# 1-POWER.net
KiCad netlist of a schematic drawn in Altium Designer
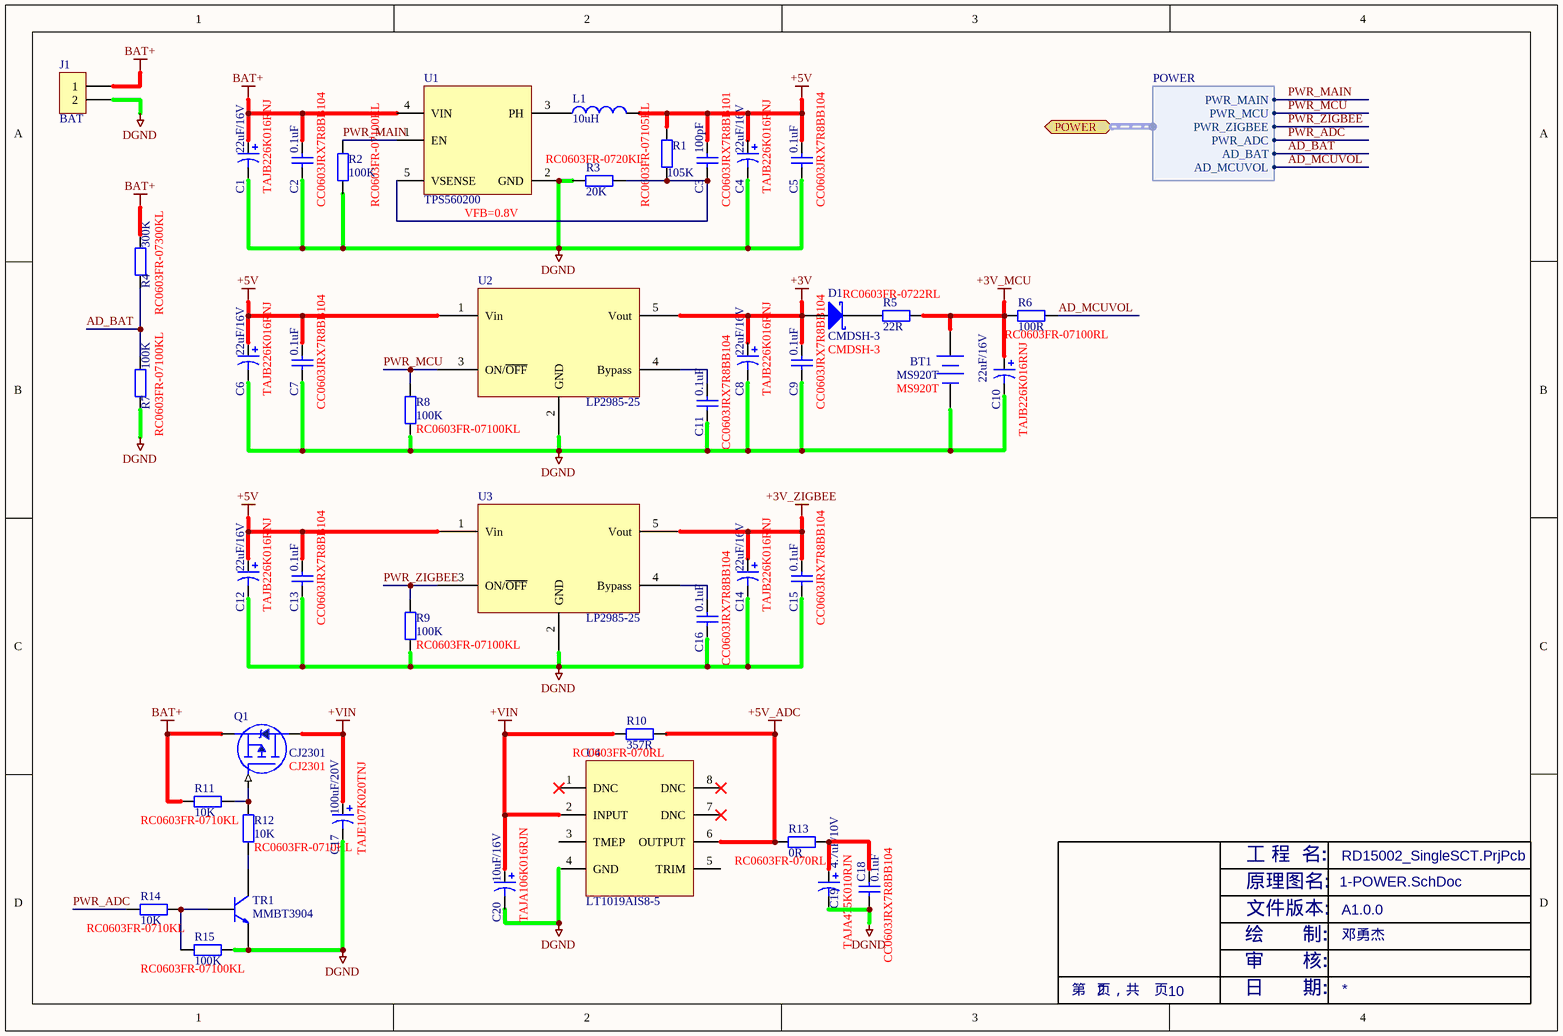
[diagram p0: 1-POWER.SchDoc]

(export (version "E")
  (design (tool "Eeschema 10.0.6"))
  (components
    (comp (ref "BT1")
      (value "MS920T")
      (footprint "MS920T")
      (description "Multicell Battery")
      (fields (field (name "TYPE NO.") "MS920T"))
      (libsource (lib "Miscellaneous Devices") (part "Battery"))
    )
    (comp (ref "C1")
      (value "22uF/16V")
      (footprint "CB3528")
      (description "Polarized Capacitor (Radial)")
      (fields (field (name "PART NO.") "TAJB226K016RNJ"))
      (libsource (lib "Miscellaneous Devices") (part "Cap Pol1"))
    )
    (comp (ref "C2")
      (value "0.1uF")
      (footprint "CC0603")
      (description "Capacitor")
      (fields (field (name "TYPE NO.") "CC0603JRX7R8BB104"))
      (libsource (lib "Miscellaneous Devices") (part "Cap"))
    )
    (comp (ref "C3")
      (value "100pF")
      (footprint "CC0603")
      (description "Capacitor")
      (fields (field (name "TYPE NO.") "CC0603JRX7R8BB101"))
      (libsource (lib "Miscellaneous Devices") (part "Cap"))
    )
    (comp (ref "C4")
      (value "22uF/16V")
      (footprint "CB3528")
      (description "Polarized Capacitor (Radial)")
      (fields (field (name "PART NO.") "TAJB226K016RNJ"))
      (libsource (lib "Miscellaneous Devices") (part "Cap Pol1"))
    )
    (comp (ref "C5")
      (value "0.1uF")
      (footprint "CC0603")
      (description "Capacitor")
      (fields (field (name "TYPE NO.") "CC0603JRX7R8BB104"))
      (libsource (lib "Miscellaneous Devices") (part "Cap"))
    )
    (comp (ref "C6")
      (value "22uF/16V")
      (footprint "CB3528")
      (description "Polarized Capacitor (Radial)")
      (fields (field (name "PART NO.") "TAJB226K016RNJ"))
      (libsource (lib "Miscellaneous Devices") (part "Cap Pol1"))
    )
    (comp (ref "C7")
      (value "0.1uF")
      (footprint "CC0603")
      (description "Capacitor")
      (fields (field (name "TYPE NO.") "CC0603JRX7R8BB104"))
      (libsource (lib "Miscellaneous Devices") (part "Cap"))
    )
    (comp (ref "C8")
      (value "22uF/16V")
      (footprint "CB3528")
      (description "Polarized Capacitor (Radial)")
      (fields (field (name "PART NO.") "TAJB226K016RNJ"))
      (libsource (lib "Miscellaneous Devices") (part "Cap Pol1"))
    )
    (comp (ref "C9")
      (value "0.1uF")
      (footprint "CC0603")
      (description "Capacitor")
      (fields (field (name "TYPE NO.") "CC0603JRX7R8BB104"))
      (libsource (lib "Miscellaneous Devices") (part "Cap"))
    )
    (comp (ref "C10")
      (value "22uF/16V")
      (footprint "CB3528")
      (description "Polarized Capacitor (Radial)")
      (fields (field (name "PART NO.") "TAJB226K016RNJ"))
      (libsource (lib "Miscellaneous Devices") (part "Cap Pol1"))
    )
    (comp (ref "C11")
      (value "0.1uF")
      (footprint "CC0603")
      (description "Capacitor")
      (fields (field (name "TYPE NO.") "CC0603JRX7R8BB104"))
      (libsource (lib "Miscellaneous Devices") (part "Cap"))
    )
    (comp (ref "C12")
      (value "22uF/16V")
      (footprint "CB3528")
      (description "Polarized Capacitor (Radial)")
      (fields (field (name "PART NO.") "TAJB226K016RNJ"))
      (libsource (lib "Miscellaneous Devices") (part "Cap Pol1"))
    )
    (comp (ref "C13")
      (value "0.1uF")
      (footprint "CC0603")
      (description "Capacitor")
      (fields (field (name "TYPE NO.") "CC0603JRX7R8BB104"))
      (libsource (lib "Miscellaneous Devices") (part "Cap"))
    )
    (comp (ref "C14")
      (value "22uF/16V")
      (footprint "CB3528")
      (description "Polarized Capacitor (Radial)")
      (fields (field (name "PART NO.") "TAJB226K016RNJ"))
      (libsource (lib "Miscellaneous Devices") (part "Cap Pol1"))
    )
    (comp (ref "C15")
      (value "0.1uF")
      (footprint "CC0603")
      (description "Capacitor")
      (fields (field (name "TYPE NO.") "CC0603JRX7R8BB104"))
      (libsource (lib "Miscellaneous Devices") (part "Cap"))
    )
    (comp (ref "C16")
      (value "0.1uF")
      (footprint "CC0603")
      (description "Capacitor")
      (fields (field (name "TYPE NO.") "CC0603JRX7R8BB104"))
      (libsource (lib "Miscellaneous Devices") (part "Cap"))
    )
    (comp (ref "C17")
      (value "100uF/20V")
      (footprint "CD7343")
      (description "Polarized Capacitor (Surface Mount)")
      (fields (field (name "TYPE NO.") "TAJE107K020TNJ"))
      (libsource (lib "Miscellaneous Devices") (part "Cap Pol3"))
    )
    (comp (ref "C18")
      (value "0.1uF")
      (footprint "CC0603")
      (description "Capacitor")
      (fields (field (name "TYPE NO.") "CC0603JRX7R8BB104"))
      (libsource (lib "Miscellaneous Devices") (part "Cap"))
    )
    (comp (ref "C19")
      (value "4.7uF/10V")
      (footprint "CA3216")
      (description "Polarized Capacitor (Radial)")
      (fields (field (name "TYPE NO.") "TAJA475K010RJN"))
      (libsource (lib "Miscellaneous Devices") (part "Cap Pol1"))
    )
    (comp (ref "C20")
      (value "10uF/16V")
      (footprint "CA3216")
      (description "Polarized Capacitor (Radial)")
      (fields (field (name "TYPE NO.") "TAJA106K016RJN"))
      (libsource (lib "Miscellaneous Devices") (part "Cap Pol1"))
    )
    (comp (ref "D1")
      (value "CMDSH-3")
      (footprint "SOD323")
      (description "Schottky Diode")
      (fields (field (name "TYPE NO.") "CMDSH-3"))
      (libsource (lib "Miscellaneous Devices") (part "D Schottky"))
    )
    (comp (ref "J1")
      (value "BAT")
      (footprint "CON2-2.54MM")
      (description "jointbar")
      (libsource (lib "AD9_WOY") (part "SIP2"))
    )
    (comp (ref "L1")
      (value "10uH")
      (footprint "SLF6025")
      (description "Inductor")
      (fields (field (name "PUBLISHER") "Altium Limited"))
      (libsource (lib "Miscellaneous Devices") (part "Inductor"))
    )
    (comp (ref "Q1")
      (value "CJ2301")
      (footprint "SOT-23W")
      (fields (field (name "TYPE NO.") "CJ2301"))
      (libsource (lib "woylib2015") (part "P-MOSFET1"))
    )
    (comp (ref "R1")
      (value "105K")
      (footprint "CC0603")
      (description "Resistor")
      (fields (field (name "TYPE NO.") "RC0603FR-07105KL"))
      (libsource (lib "") (part "Res2_1"))
    )
    (comp (ref "R2")
      (value "100K")
      (footprint "CC0603")
      (description "Resistor")
      (fields (field (name "TYPE NO.") "RC0603FR-07100KL"))
      (libsource (lib "") (part "Res2_1"))
    )
    (comp (ref "R3")
      (value "20K")
      (footprint "CC0603")
      (description "Resistor")
      (fields (field (name "TYPE NO.") "RC0603FR-0720KL"))
      (libsource (lib "Miscellaneous Devices") (part "Res2"))
    )
    (comp (ref "R4")
      (value "300K")
      (footprint "CC0603")
      (description "Resistor")
      (fields (field (name "TYPE NO.") "RC0603FR-07300KL"))
      (libsource (lib "") (part "Res2_1"))
    )
    (comp (ref "R5")
      (value "22R")
      (footprint "CC0603")
      (description "Resistor")
      (fields (field (name "TYPE NO.") "RC0603FR-0722RL"))
      (libsource (lib "Miscellaneous Devices") (part "Res2"))
    )
    (comp (ref "R6")
      (value "100R")
      (footprint "CC0603")
      (description "Resistor")
      (fields (field (name "TYPE NO.") "RC0603FR-07100RL"))
      (libsource (lib "Miscellaneous Devices") (part "Res2"))
    )
    (comp (ref "R7")
      (value "100K")
      (footprint "CC0603")
      (description "Resistor")
      (fields (field (name "TYPE NO.") "RC0603FR-07100KL"))
      (libsource (lib "") (part "Res2_1"))
    )
    (comp (ref "R8")
      (value "100K")
      (footprint "CC0603")
      (description "Resistor")
      (fields (field (name "TYPE NO.") "RC0603FR-07100KL"))
      (libsource (lib "") (part "Res2_1"))
    )
    (comp (ref "R9")
      (value "100K")
      (footprint "CC0603")
      (description "Resistor")
      (fields (field (name "TYPE NO.") "RC0603FR-07100KL"))
      (libsource (lib "") (part "Res2_1"))
    )
    (comp (ref "R10")
      (value "357R")
      (footprint "CC0603")
      (description "Resistor")
      (fields (field (name "TYPE NO.") "RC0603FR-070RL"))
      (libsource (lib "Miscellaneous Devices") (part "Res2"))
    )
    (comp (ref "R11")
      (value "10K")
      (footprint "CC0603")
      (description "Resistor")
      (fields (field (name "TYPE NO.") "RC0603FR-0710KL"))
      (libsource (lib "Miscellaneous Devices") (part "Res2"))
    )
    (comp (ref "R12")
      (value "10K")
      (footprint "CC0603")
      (description "Resistor")
      (fields (field (name "TYPE NO.") "RC0603FR-0710KL"))
      (libsource (lib "") (part "Res2_1"))
    )
    (comp (ref "R13")
      (value "0R")
      (footprint "CC0603")
      (description "Resistor")
      (fields (field (name "TYPE NO.") "RC0603FR-070RL"))
      (libsource (lib "Miscellaneous Devices") (part "Res2"))
    )
    (comp (ref "R14")
      (value "10K")
      (footprint "CC0603")
      (description "Resistor")
      (fields (field (name "TYPE NO.") "RC0603FR-0710KL"))
      (libsource (lib "Miscellaneous Devices") (part "Res2"))
    )
    (comp (ref "R15")
      (value "100K")
      (footprint "CC0603")
      (description "Resistor")
      (fields (field (name "TYPE NO.") "RC0603FR-07100KL"))
      (libsource (lib "Miscellaneous Devices") (part "Res2"))
    )
    (comp (ref "TR1") (value "MMBT3904") (footprint "SOT-23W") (libsource (lib "Discrete") (part "NPN")))
    (comp (ref "U1") (value "TPS560200") (footprint "SOT-23-5") (libsource (lib "IC") (part "TPS560200")))
    (comp (ref "U2") (value "LP2985-25") (footprint "SOT-23-5") (libsource (lib "IC") (part "LP2985")))
    (comp (ref "U3") (value "LP2985-25") (footprint "SOT-23-5") (libsource (lib "IC") (part "LP2985")))
    (comp (ref "U4") (value "LT1019AIS8-5") (footprint "SO-8") (libsource (lib "IC") (part "LT1019AIS8-5")))
  )
  (nets
    (net (code "2") (name "+3V") (class "Default")
      (node (ref "C8") (pin "1") (pinfunction "1_1") (pintype "passive"))
      (node (ref "C9") (pin "2") (pinfunction "2_2") (pintype "passive"))
      (node (ref "D1") (pin "1") (pinfunction "A_1") (pintype "passive"))
      (node (ref "U2") (pin "5") (pinfunction "Vout_5") (pintype "passive"))
    )
    (net (code "3") (name "+3V_MCU") (class "Default")
      (node (ref "BT1") (pin "1") (pinfunction "+_1") (pintype "passive"))
      (node (ref "C10") (pin "1") (pinfunction "1_1") (pintype "passive"))
      (node (ref "R5") (pin "1") (pinfunction "1_1") (pintype "passive"))
      (node (ref "R6") (pin "2") (pinfunction "2_2") (pintype "passive"))
    )
    (net (code "4") (name "+3V_ZIGBEE") (class "Default")
      (node (ref "C14") (pin "1") (pinfunction "1_1") (pintype "passive"))
      (node (ref "C15") (pin "2") (pinfunction "2_2") (pintype "passive"))
      (node (ref "U3") (pin "5") (pinfunction "Vout_5") (pintype "passive"))
    )
    (net (code "5") (name "+5V") (class "Default")
      (node (ref "C12") (pin "1") (pinfunction "1_1") (pintype "passive"))
      (node (ref "C13") (pin "2") (pinfunction "2_2") (pintype "passive"))
      (node (ref "C3") (pin "2") (pinfunction "2_2") (pintype "passive"))
      (node (ref "C4") (pin "1") (pinfunction "1_1") (pintype "passive"))
      (node (ref "C5") (pin "2") (pinfunction "2_2") (pintype "passive"))
      (node (ref "C6") (pin "1") (pinfunction "1_1") (pintype "passive"))
      (node (ref "C7") (pin "2") (pinfunction "2_2") (pintype "passive"))
      (node (ref "L1") (pin "2") (pinfunction "2_2") (pintype "passive"))
      (node (ref "R1") (pin "1") (pinfunction "1_1") (pintype "passive"))
      (node (ref "U2") (pin "1") (pinfunction "Vin_1") (pintype "passive"))
      (node (ref "U3") (pin "1") (pinfunction "Vin_1") (pintype "passive"))
    )
    (net (code "6") (name "+5V_ADC") (class "Default")
      (node (ref "R10") (pin "1") (pinfunction "1_1") (pintype "passive"))
      (node (ref "R13") (pin "2") (pinfunction "2_2") (pintype "passive"))
      (node (ref "U4") (pin "6") (pinfunction "OUTPUT_6") (pintype "passive"))
    )
    (net (code "7") (name "+VIN") (class "Default")
      (node (ref "C17") (pin "1") (pinfunction "1_1") (pintype "passive"))
      (node (ref "C20") (pin "1") (pinfunction "1_1") (pintype "passive"))
      (node (ref "Q1") (pin "3") (pinfunction "DRAIN_3") (pintype "passive"))
      (node (ref "R10") (pin "2") (pinfunction "2_2") (pintype "passive"))
      (node (ref "U4") (pin "2") (pinfunction "INPUT_2") (pintype "passive"))
    )
    (net (code "8") (name "/AD_BAT") (class "Default")
      (node (ref "R4") (pin "2") (pinfunction "2_2") (pintype "passive"))
      (node (ref "R7") (pin "1") (pinfunction "1_1") (pintype "passive"))
    )
    (net (code "9") (name "/AD_MCUVOL") (class "Default")
      (node (ref "R6") (pin "1") (pinfunction "1_1") (pintype "passive"))
    )
    (net (code "10") (name "/PWR_ADC") (class "Default")
      (node (ref "R14") (pin "2") (pinfunction "2_2") (pintype "passive"))
    )
    (net (code "11") (name "/PWR_MAIN") (class "Default")
      (node (ref "R2") (pin "1") (pinfunction "1_1") (pintype "passive"))
      (node (ref "U1") (pin "1") (pinfunction "EN_1") (pintype "passive"))
    )
    (net (code "12") (name "/PWR_MCU") (class "Default")
      (node (ref "R8") (pin "1") (pinfunction "1_1") (pintype "passive"))
      (node (ref "U2") (pin "3") (pinfunction "ON/~{OFF}_3") (pintype "passive"))
    )
    (net (code "13") (name "/PWR_ZIGBEE") (class "Default")
      (node (ref "R9") (pin "1") (pinfunction "1_1") (pintype "passive"))
      (node (ref "U3") (pin "3") (pinfunction "ON/~{OFF}_3") (pintype "passive"))
    )
    (net (code "15") (name "BAT+") (class "Default")
      (node (ref "C1") (pin "1") (pinfunction "1_1") (pintype "passive"))
      (node (ref "C2") (pin "2") (pinfunction "2_2") (pintype "passive"))
      (node (ref "J1") (pin "1") (pinfunction "1_1") (pintype "passive"))
      (node (ref "Q1") (pin "2") (pinfunction "SOURCE_2") (pintype "passive"))
      (node (ref "R11") (pin "2") (pinfunction "2_2") (pintype "passive"))
      (node (ref "R4") (pin "1") (pinfunction "1_1") (pintype "passive"))
      (node (ref "U1") (pin "4") (pinfunction "VIN_4") (pintype "passive"))
    )
    (net (code "16") (name "DGND") (class "Default")
      (node (ref "BT1") (pin "2") (pinfunction "-_2") (pintype "passive"))
      (node (ref "C1") (pin "2") (pinfunction "2_2") (pintype "passive"))
      (node (ref "C10") (pin "2") (pinfunction "2_2") (pintype "passive"))
      (node (ref "C11") (pin "1") (pinfunction "1_1") (pintype "passive"))
      (node (ref "C12") (pin "2") (pinfunction "2_2") (pintype "passive"))
      (node (ref "C13") (pin "1") (pinfunction "1_1") (pintype "passive"))
      (node (ref "C14") (pin "2") (pinfunction "2_2") (pintype "passive"))
      (node (ref "C15") (pin "1") (pinfunction "1_1") (pintype "passive"))
      (node (ref "C16") (pin "1") (pinfunction "1_1") (pintype "passive"))
      (node (ref "C17") (pin "2") (pinfunction "2_2") (pintype "passive"))
      (node (ref "C18") (pin "1") (pinfunction "1_1") (pintype "passive"))
      (node (ref "C19") (pin "2") (pinfunction "2_2") (pintype "passive"))
      (node (ref "C2") (pin "1") (pinfunction "1_1") (pintype "passive"))
      (node (ref "C20") (pin "2") (pinfunction "2_2") (pintype "passive"))
      (node (ref "C4") (pin "2") (pinfunction "2_2") (pintype "passive"))
      (node (ref "C5") (pin "1") (pinfunction "1_1") (pintype "passive"))
      (node (ref "C6") (pin "2") (pinfunction "2_2") (pintype "passive"))
      (node (ref "C7") (pin "1") (pinfunction "1_1") (pintype "passive"))
      (node (ref "C8") (pin "2") (pinfunction "2_2") (pintype "passive"))
      (node (ref "C9") (pin "1") (pinfunction "1_1") (pintype "passive"))
      (node (ref "J1") (pin "2") (pinfunction "2_2") (pintype "passive"))
      (node (ref "R15") (pin "1") (pinfunction "1_1") (pintype "passive"))
      (node (ref "R2") (pin "2") (pinfunction "2_2") (pintype "passive"))
      (node (ref "R3") (pin "2") (pinfunction "2_2") (pintype "passive"))
      (node (ref "R7") (pin "2") (pinfunction "2_2") (pintype "passive"))
      (node (ref "R8") (pin "2") (pinfunction "2_2") (pintype "passive"))
      (node (ref "R9") (pin "2") (pinfunction "2_2") (pintype "passive"))
      (node (ref "TR1") (pin "2") (pinfunction "2_2") (pintype "passive"))
      (node (ref "U1") (pin "2") (pinfunction "GND_2") (pintype "passive"))
      (node (ref "U2") (pin "2") (pinfunction "GND_2") (pintype "passive"))
      (node (ref "U3") (pin "2") (pinfunction "GND_2") (pintype "passive"))
      (node (ref "U4") (pin "4") (pinfunction "GND_4") (pintype "passive"))
    )
    (net (code "17") (name "Net-(C18-Pad2)") (class "Default")
      (node (ref "C18") (pin "2") (pinfunction "2_2") (pintype "passive"))
      (node (ref "C19") (pin "1") (pinfunction "1_1") (pintype "passive"))
      (node (ref "R13") (pin "1") (pinfunction "1_1") (pintype "passive"))
    )
    (net (code "18") (name "Net-(D1-K)") (class "Default")
      (node (ref "D1") (pin "2") (pinfunction "K_2") (pintype "passive"))
      (node (ref "R5") (pin "2") (pinfunction "2_2") (pintype "passive"))
    )
    (net (code "19") (name "Net-(Q1-GATE)") (class "Default")
      (node (ref "Q1") (pin "1") (pinfunction "GATE_1") (pintype "input"))
      (node (ref "R11") (pin "1") (pinfunction "1_1") (pintype "passive"))
      (node (ref "R12") (pin "1") (pinfunction "1_1") (pintype "passive"))
    )
    (net (code "20") (name "Net-(R12-Pad2)") (class "Default")
      (node (ref "R12") (pin "2") (pinfunction "2_2") (pintype "passive"))
      (node (ref "TR1") (pin "3") (pinfunction "3_3") (pintype "passive"))
    )
    (net (code "21") (name "Net-(R14-Pad1)") (class "Default")
      (node (ref "R14") (pin "1") (pinfunction "1_1") (pintype "passive"))
      (node (ref "R15") (pin "2") (pinfunction "2_2") (pintype "passive"))
      (node (ref "TR1") (pin "1") (pinfunction "1_1") (pintype "passive"))
    )
    (net (code "22") (name "Net-(U1-PH)") (class "Default")
      (node (ref "L1") (pin "1") (pinfunction "1_1") (pintype "passive"))
      (node (ref "U1") (pin "3") (pinfunction "PH_3") (pintype "passive"))
    )
    (net (code "23") (name "Net-(U1-VSENSE)") (class "Default")
      (node (ref "C3") (pin "1") (pinfunction "1_1") (pintype "passive"))
      (node (ref "R1") (pin "2") (pinfunction "2_2") (pintype "passive"))
      (node (ref "R3") (pin "1") (pinfunction "1_1") (pintype "passive"))
      (node (ref "U1") (pin "5") (pinfunction "VSENSE_5") (pintype "passive"))
    )
    (net (code "24") (name "Net-(U2-Bypass)") (class "Default")
      (node (ref "C11") (pin "2") (pinfunction "2_2") (pintype "passive"))
      (node (ref "U2") (pin "4") (pinfunction "Bypass_4") (pintype "passive"))
    )
    (net (code "25") (name "Net-(U3-Bypass)") (class "Default")
      (node (ref "C16") (pin "2") (pinfunction "2_2") (pintype "passive"))
      (node (ref "U3") (pin "4") (pinfunction "Bypass_4") (pintype "passive"))
    )
    (net (code "26") (name "unconnected-(U4-DNC-Pad1)") (class "Default")
      (node (ref "U4") (pin "1") (pinfunction "DNC_1") (pintype "passive+no_connect"))
    )
    (net (code "27") (name "unconnected-(U4-DNC-Pad7)") (class "Default")
      (node (ref "U4") (pin "7") (pinfunction "DNC_7") (pintype "passive+no_connect"))
    )
    (net (code "28") (name "unconnected-(U4-DNC-Pad8)") (class "Default")
      (node (ref "U4") (pin "8") (pinfunction "DNC_8") (pintype "passive+no_connect"))
    )
    (net (code "29") (name "unconnected-(U4-TMEP-Pad3)") (class "Default")
      (node (ref "U4") (pin "3") (pinfunction "TMEP_3") (pintype "passive"))
    )
    (net (code "30") (name "unconnected-(U4-TRIM-Pad5)") (class "Default")
      (node (ref "U4") (pin "5") (pinfunction "TRIM_5") (pintype "passive"))
    )
  )
)
